# 5-3_fpga_bank_14-16.net
KiCad netlist of a schematic drawn in Altium Designer
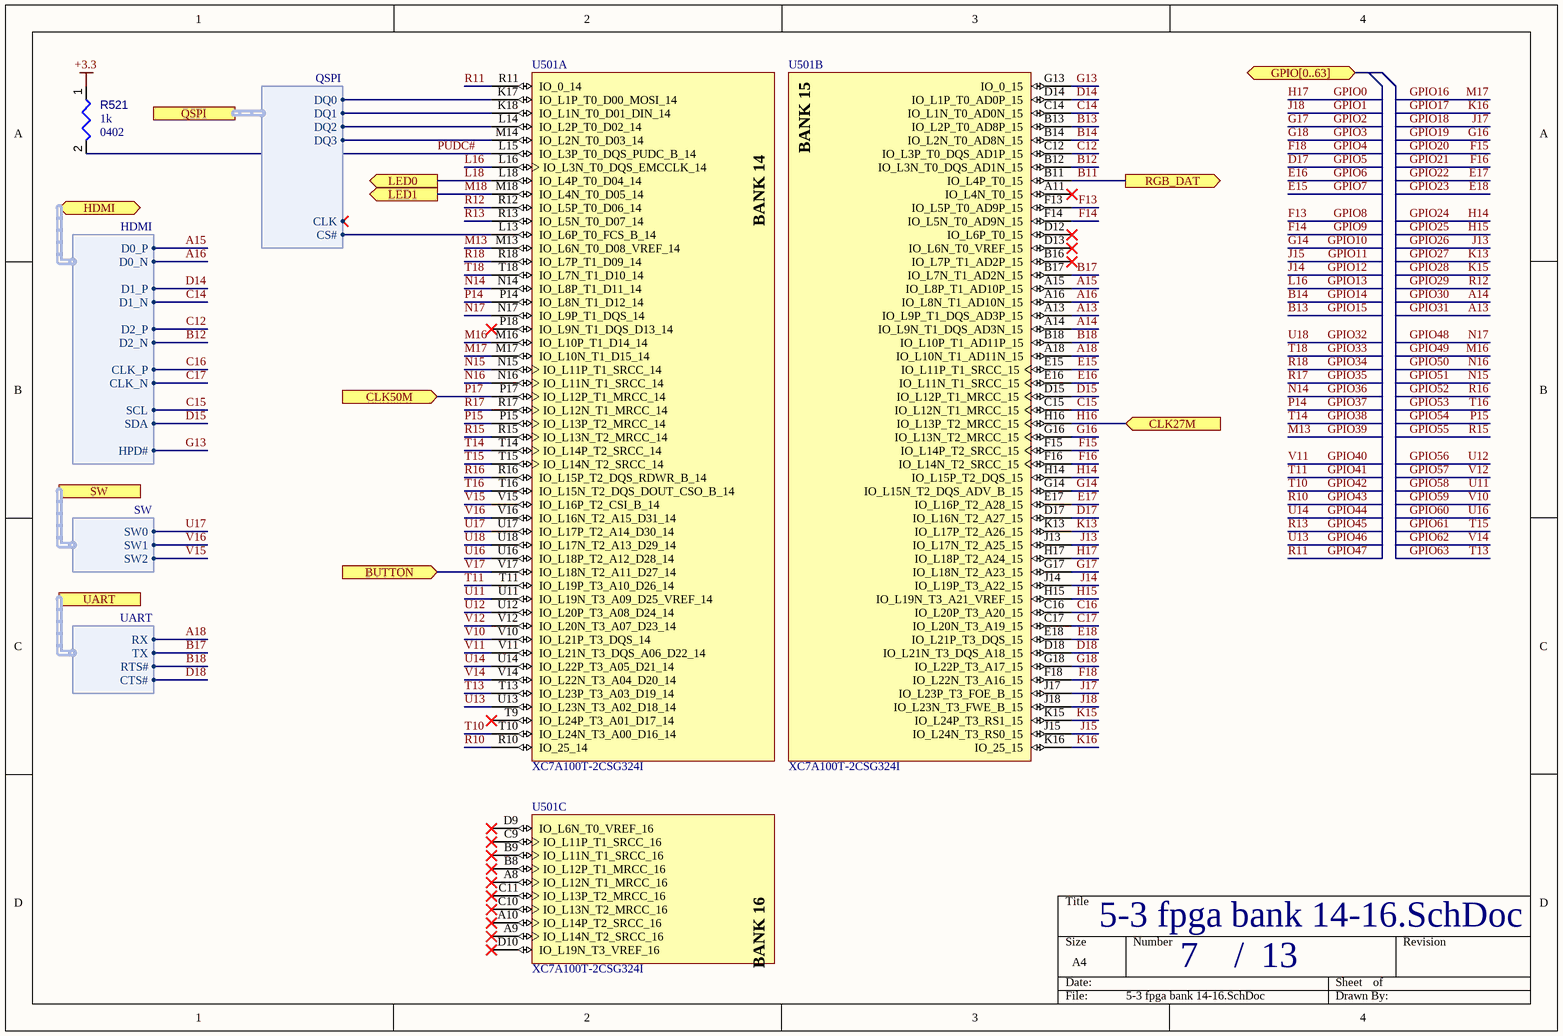
[diagram p0: 5-3 fpga bank 14-16.SchDoc]

(export (version "E")
  (design (tool "Eeschema 10.0.6"))
  (components
    (comp (ref "R521")
      (value "1k")
      (footprint "RESC0402(1005)_L")
      (description "Resistor")
      (fields (field (name "CASE/PACKAGE") "0402") (field (name "Comment") "Resistors,0402,1k"))
      (libsource (lib "UBC Uncrewed Aircraft Systems") (part "RES-2"))
    )
    (comp (ref "U501")
      (value "XC7A100T-2CSG324I")
      (footprint "CSG324")
      (description "Artix-7 FPGA, 210 User I/Os, 0 GTP, 324-Ball BGA, Speed Grade 2, Extended Grade, Pb-Free")
      (fields (field (name "MANUFACTURER") "Xilinx") (field (name "GENERIC PART NUMBER") "XC7A100T"))
      (libsource (lib "") (part "XNLX-XC7A100T-XNLX-CSG324_1"))
    )
  )
  (nets
    (net (code "5") (name "+3.3") (class "Default")
      (node (ref "R521") (pin "1") (pinfunction "1_1") (pintype "passive"))
    )
    (net (code "6") (name "/A15") (class "Default")
      (node (ref "U501") (pin "A15") (pinfunction "IO_L8P_T1_AD10P_15_A15") (pintype "bidirectional"))
    )
    (net (code "7") (name "/A16") (class "Default")
      (node (ref "U501") (pin "A16") (pinfunction "IO_L8N_T1_AD10N_15_A16") (pintype "bidirectional"))
    )
    (net (code "8") (name "/A18") (class "Default")
      (node (ref "U501") (pin "A18") (pinfunction "IO_L10N_T1_AD11N_15_A18") (pintype "bidirectional"))
    )
    (net (code "9") (name "/B11") (class "Default")
      (node (ref "U501") (pin "B11") (pinfunction "IO_L4P_T0_15_B11") (pintype "bidirectional"))
    )
    (net (code "10") (name "/B12") (class "Default")
      (node (ref "U501") (pin "B12") (pinfunction "IO_L3N_T0_DQS_AD1N_15_B12") (pintype "bidirectional"))
    )
    (net (code "11") (name "/B17") (class "Default")
      (node (ref "U501") (pin "B17") (pinfunction "IO_L7N_T1_AD2N_15_B17") (pintype "bidirectional"))
    )
    (net (code "12") (name "/B18") (class "Default")
      (node (ref "U501") (pin "B18") (pinfunction "IO_L10P_T1_AD11P_15_B18") (pintype "bidirectional"))
    )
    (net (code "13") (name "/C12") (class "Default")
      (node (ref "U501") (pin "C12") (pinfunction "IO_L3P_T0_DQS_AD1P_15_C12") (pintype "bidirectional"))
    )
    (net (code "14") (name "/C14") (class "Default")
      (node (ref "U501") (pin "C14") (pinfunction "IO_L1N_T0_AD0N_15_C14") (pintype "bidirectional"))
    )
    (net (code "15") (name "/C15") (class "Default")
      (node (ref "U501") (pin "C15") (pinfunction "IO_L12N_T1_MRCC_15_C15") (pintype "bidirectional"))
    )
    (net (code "16") (name "/C16") (class "Default")
      (node (ref "U501") (pin "C16") (pinfunction "IO_L20P_T3_A20_15_C16") (pintype "bidirectional"))
    )
    (net (code "17") (name "/C17") (class "Default")
      (node (ref "U501") (pin "C17") (pinfunction "IO_L20N_T3_A19_15_C17") (pintype "bidirectional"))
    )
    (net (code "18") (name "/CS#") (class "Default")
      (node (ref "U501") (pin "L13") (pinfunction "IO_L6P_T0_FCS_B_14_L13") (pintype "bidirectional"))
    )
    (net (code "19") (name "/D14") (class "Default")
      (node (ref "U501") (pin "D14") (pinfunction "IO_L1P_T0_AD0P_15_D14") (pintype "bidirectional"))
    )
    (net (code "20") (name "/D15") (class "Default")
      (node (ref "U501") (pin "D15") (pinfunction "IO_L12P_T1_MRCC_15_D15") (pintype "bidirectional"))
    )
    (net (code "21") (name "/D18") (class "Default")
      (node (ref "U501") (pin "D18") (pinfunction "IO_L21N_T3_DQS_A18_15_D18") (pintype "bidirectional"))
    )
    (net (code "22") (name "/DQ0") (class "Default")
      (node (ref "U501") (pin "K17") (pinfunction "IO_L1P_T0_D00_MOSI_14_K17") (pintype "bidirectional"))
    )
    (net (code "23") (name "/DQ1") (class "Default")
      (node (ref "U501") (pin "K18") (pinfunction "IO_L1N_T0_D01_DIN_14_K18") (pintype "bidirectional"))
    )
    (net (code "24") (name "/DQ2") (class "Default")
      (node (ref "U501") (pin "L14") (pinfunction "IO_L2P_T0_D02_14_L14") (pintype "bidirectional"))
    )
    (net (code "25") (name "/DQ3") (class "Default")
      (node (ref "U501") (pin "M14") (pinfunction "IO_L2N_T0_D03_14_M14") (pintype "bidirectional"))
    )
    (net (code "26") (name "/G13") (class "Default")
      (node (ref "U501") (pin "G13") (pinfunction "IO_0_15_G13") (pintype "bidirectional"))
    )
    (net (code "27") (name "/GPIO0") (class "Default")
      (node (ref "U501") (pin "H17") (pinfunction "IO_L18P_T2_A24_15_H17") (pintype "bidirectional"))
    )
    (net (code "28") (name "/GPIO1") (class "Default")
      (node (ref "U501") (pin "J18") (pinfunction "IO_L23N_T3_FWE_B_15_J18") (pintype "bidirectional"))
    )
    (net (code "29") (name "/GPIO2") (class "Default")
      (node (ref "U501") (pin "G17") (pinfunction "IO_L18N_T2_A23_15_G17") (pintype "bidirectional"))
    )
    (net (code "30") (name "/GPIO3") (class "Default")
      (node (ref "U501") (pin "G18") (pinfunction "IO_L22P_T3_A17_15_G18") (pintype "bidirectional"))
    )
    (net (code "31") (name "/GPIO4") (class "Default")
      (node (ref "U501") (pin "F18") (pinfunction "IO_L22N_T3_A16_15_F18") (pintype "bidirectional"))
    )
    (net (code "32") (name "/GPIO5") (class "Default")
      (node (ref "U501") (pin "D17") (pinfunction "IO_L16N_T2_A27_15_D17") (pintype "bidirectional"))
    )
    (net (code "33") (name "/GPIO6") (class "Default")
      (node (ref "U501") (pin "E16") (pinfunction "IO_L11N_T1_SRCC_15_E16") (pintype "bidirectional"))
    )
    (net (code "34") (name "/GPIO7") (class "Default")
      (node (ref "U501") (pin "E15") (pinfunction "IO_L11P_T1_SRCC_15_E15") (pintype "bidirectional"))
    )
    (net (code "35") (name "/GPIO8") (class "Default")
      (node (ref "U501") (pin "F13") (pinfunction "IO_L5P_T0_AD9P_15_F13") (pintype "bidirectional"))
    )
    (net (code "36") (name "/GPIO9") (class "Default")
      (node (ref "U501") (pin "F14") (pinfunction "IO_L5N_T0_AD9N_15_F14") (pintype "bidirectional"))
    )
    (net (code "37") (name "/GPIO10") (class "Default")
      (node (ref "U501") (pin "G14") (pinfunction "IO_L15N_T2_DQS_ADV_B_15_G14") (pintype "bidirectional"))
    )
    (net (code "38") (name "/GPIO11") (class "Default")
      (node (ref "U501") (pin "J15") (pinfunction "IO_L24N_T3_RS0_15_J15") (pintype "bidirectional"))
    )
    (net (code "39") (name "/GPIO12") (class "Default")
      (node (ref "U501") (pin "J14") (pinfunction "IO_L19P_T3_A22_15_J14") (pintype "bidirectional"))
    )
    (net (code "40") (name "/GPIO13") (class "Default")
      (node (ref "U501") (pin "L16") (pinfunction "IO_L3N_T0_DQS_EMCCLK_14_L16") (pintype "bidirectional"))
    )
    (net (code "41") (name "/GPIO14") (class "Default")
      (node (ref "U501") (pin "B14") (pinfunction "IO_L2N_T0_AD8N_15_B14") (pintype "bidirectional"))
    )
    (net (code "42") (name "/GPIO15") (class "Default")
      (node (ref "U501") (pin "B13") (pinfunction "IO_L2P_T0_AD8P_15_B13") (pintype "bidirectional"))
    )
    (net (code "43") (name "/GPIO16") (class "Default")
      (node (ref "U501") (pin "M17") (pinfunction "IO_L10N_T1_D15_14_M17") (pintype "bidirectional"))
    )
    (net (code "44") (name "/GPIO17") (class "Default")
      (node (ref "U501") (pin "K16") (pinfunction "IO_25_15_K16") (pintype "bidirectional"))
    )
    (net (code "45") (name "/GPIO18") (class "Default")
      (node (ref "U501") (pin "J17") (pinfunction "IO_L23P_T3_FOE_B_15_J17") (pintype "bidirectional"))
    )
    (net (code "46") (name "/GPIO19") (class "Default")
      (node (ref "U501") (pin "G16") (pinfunction "IO_L13N_T2_MRCC_15_G16") (pintype "bidirectional"))
    )
    (net (code "47") (name "/GPIO20") (class "Default")
      (node (ref "U501") (pin "F15") (pinfunction "IO_L14P_T2_SRCC_15_F15") (pintype "bidirectional"))
    )
    (net (code "48") (name "/GPIO21") (class "Default")
      (node (ref "U501") (pin "F16") (pinfunction "IO_L14N_T2_SRCC_15_F16") (pintype "bidirectional"))
    )
    (net (code "49") (name "/GPIO22") (class "Default")
      (node (ref "U501") (pin "E17") (pinfunction "IO_L16P_T2_A28_15_E17") (pintype "bidirectional"))
    )
    (net (code "50") (name "/GPIO23") (class "Default")
      (node (ref "U501") (pin "E18") (pinfunction "IO_L21P_T3_DQS_15_E18") (pintype "bidirectional"))
    )
    (net (code "51") (name "/GPIO24") (class "Default")
      (node (ref "U501") (pin "H14") (pinfunction "IO_L15P_T2_DQS_15_H14") (pintype "bidirectional"))
    )
    (net (code "52") (name "/GPIO25") (class "Default")
      (node (ref "U501") (pin "H15") (pinfunction "IO_L19N_T3_A21_VREF_15_H15") (pintype "bidirectional"))
    )
    (net (code "53") (name "/GPIO26") (class "Default")
      (node (ref "U501") (pin "J13") (pinfunction "IO_L17N_T2_A25_15_J13") (pintype "bidirectional"))
    )
    (net (code "54") (name "/GPIO27") (class "Default")
      (node (ref "U501") (pin "K13") (pinfunction "IO_L17P_T2_A26_15_K13") (pintype "bidirectional"))
    )
    (net (code "55") (name "/GPIO28") (class "Default")
      (node (ref "U501") (pin "K15") (pinfunction "IO_L24P_T3_RS1_15_K15") (pintype "bidirectional"))
    )
    (net (code "56") (name "/GPIO29") (class "Default")
      (node (ref "U501") (pin "R12") (pinfunction "IO_L5P_T0_D06_14_R12") (pintype "bidirectional"))
    )
    (net (code "57") (name "/GPIO30") (class "Default")
      (node (ref "U501") (pin "A14") (pinfunction "IO_L9N_T1_DQS_AD3N_15_A14") (pintype "bidirectional"))
    )
    (net (code "58") (name "/GPIO31") (class "Default")
      (node (ref "U501") (pin "A13") (pinfunction "IO_L9P_T1_DQS_AD3P_15_A13") (pintype "bidirectional"))
    )
    (net (code "59") (name "/GPIO32") (class "Default")
      (node (ref "U501") (pin "U18") (pinfunction "IO_L17N_T2_A13_D29_14_U18") (pintype "bidirectional"))
    )
    (net (code "60") (name "/GPIO33") (class "Default")
      (node (ref "U501") (pin "T18") (pinfunction "IO_L7N_T1_D10_14_T18") (pintype "bidirectional"))
    )
    (net (code "61") (name "/GPIO34") (class "Default")
      (node (ref "U501") (pin "R18") (pinfunction "IO_L7P_T1_D09_14_R18") (pintype "bidirectional"))
    )
    (net (code "62") (name "/GPIO35") (class "Default")
      (node (ref "U501") (pin "R17") (pinfunction "IO_L12N_T1_MRCC_14_R17") (pintype "bidirectional"))
    )
    (net (code "63") (name "/GPIO36") (class "Default")
      (node (ref "U501") (pin "N14") (pinfunction "IO_L8P_T1_D11_14_N14") (pintype "bidirectional"))
    )
    (net (code "64") (name "/GPIO37") (class "Default")
      (node (ref "U501") (pin "P14") (pinfunction "IO_L8N_T1_D12_14_P14") (pintype "bidirectional"))
    )
    (net (code "65") (name "/GPIO38") (class "Default")
      (node (ref "U501") (pin "T14") (pinfunction "IO_L14P_T2_SRCC_14_T14") (pintype "bidirectional"))
    )
    (net (code "66") (name "/GPIO39") (class "Default")
      (node (ref "U501") (pin "M13") (pinfunction "IO_L6N_T0_D08_VREF_14_M13") (pintype "bidirectional"))
    )
    (net (code "67") (name "/GPIO40") (class "Default")
      (node (ref "U501") (pin "V11") (pinfunction "IO_L21N_T3_DQS_A06_D22_14_V11") (pintype "bidirectional"))
    )
    (net (code "68") (name "/GPIO41") (class "Default")
      (node (ref "U501") (pin "T11") (pinfunction "IO_L19P_T3_A10_D26_14_T11") (pintype "bidirectional"))
    )
    (net (code "69") (name "/GPIO42") (class "Default")
      (node (ref "U501") (pin "T10") (pinfunction "IO_L24N_T3_A00_D16_14_T10") (pintype "bidirectional"))
    )
    (net (code "70") (name "/GPIO43") (class "Default")
      (node (ref "U501") (pin "R10") (pinfunction "IO_25_14_R10") (pintype "bidirectional"))
    )
    (net (code "71") (name "/GPIO44") (class "Default")
      (node (ref "U501") (pin "U14") (pinfunction "IO_L22P_T3_A05_D21_14_U14") (pintype "bidirectional"))
    )
    (net (code "72") (name "/GPIO45") (class "Default")
      (node (ref "U501") (pin "R13") (pinfunction "IO_L5N_T0_D07_14_R13") (pintype "bidirectional"))
    )
    (net (code "73") (name "/GPIO46") (class "Default")
      (node (ref "U501") (pin "U13") (pinfunction "IO_L23N_T3_A02_D18_14_U13") (pintype "bidirectional"))
    )
    (net (code "74") (name "/GPIO47") (class "Default")
      (node (ref "U501") (pin "R11") (pinfunction "IO_0_14_R11") (pintype "bidirectional"))
    )
    (net (code "75") (name "/GPIO48") (class "Default")
      (node (ref "U501") (pin "N17") (pinfunction "IO_L9P_T1_DQS_14_N17") (pintype "bidirectional"))
    )
    (net (code "76") (name "/GPIO49") (class "Default")
      (node (ref "U501") (pin "M16") (pinfunction "IO_L10P_T1_D14_14_M16") (pintype "bidirectional"))
    )
    (net (code "77") (name "/GPIO50") (class "Default")
      (node (ref "U501") (pin "N16") (pinfunction "IO_L11N_T1_SRCC_14_N16") (pintype "bidirectional"))
    )
    (net (code "78") (name "/GPIO51") (class "Default")
      (node (ref "U501") (pin "N15") (pinfunction "IO_L11P_T1_SRCC_14_N15") (pintype "bidirectional"))
    )
    (net (code "79") (name "/GPIO52") (class "Default")
      (node (ref "U501") (pin "R16") (pinfunction "IO_L15P_T2_DQS_RDWR_B_14_R16") (pintype "bidirectional"))
    )
    (net (code "80") (name "/GPIO53") (class "Default")
      (node (ref "U501") (pin "T16") (pinfunction "IO_L15N_T2_DQS_DOUT_CSO_B_14_T16") (pintype "bidirectional"))
    )
    (net (code "81") (name "/GPIO54") (class "Default")
      (node (ref "U501") (pin "P15") (pinfunction "IO_L13P_T2_MRCC_14_P15") (pintype "bidirectional"))
    )
    (net (code "82") (name "/GPIO55") (class "Default")
      (node (ref "U501") (pin "R15") (pinfunction "IO_L13N_T2_MRCC_14_R15") (pintype "bidirectional"))
    )
    (net (code "83") (name "/GPIO56") (class "Default")
      (node (ref "U501") (pin "U12") (pinfunction "IO_L20P_T3_A08_D24_14_U12") (pintype "bidirectional"))
    )
    (net (code "84") (name "/GPIO57") (class "Default")
      (node (ref "U501") (pin "V12") (pinfunction "IO_L20N_T3_A07_D23_14_V12") (pintype "bidirectional"))
    )
    (net (code "85") (name "/GPIO58") (class "Default")
      (node (ref "U501") (pin "U11") (pinfunction "IO_L19N_T3_A09_D25_VREF_14_U11") (pintype "bidirectional"))
    )
    (net (code "86") (name "/GPIO59") (class "Default")
      (node (ref "U501") (pin "V10") (pinfunction "IO_L21P_T3_DQS_14_V10") (pintype "bidirectional"))
    )
    (net (code "87") (name "/GPIO60") (class "Default")
      (node (ref "U501") (pin "U16") (pinfunction "IO_L18P_T2_A12_D28_14_U16") (pintype "bidirectional"))
    )
    (net (code "88") (name "/GPIO61") (class "Default")
      (node (ref "U501") (pin "T15") (pinfunction "IO_L14N_T2_SRCC_14_T15") (pintype "bidirectional"))
    )
    (net (code "89") (name "/GPIO62") (class "Default")
      (node (ref "U501") (pin "V14") (pinfunction "IO_L22N_T3_A04_D20_14_V14") (pintype "bidirectional"))
    )
    (net (code "90") (name "/GPIO63") (class "Default")
      (node (ref "U501") (pin "T13") (pinfunction "IO_L23P_T3_A03_D19_14_T13") (pintype "bidirectional"))
    )
    (net (code "92") (name "/H16") (class "Default")
      (node (ref "U501") (pin "H16") (pinfunction "IO_L13P_T2_MRCC_15_H16") (pintype "bidirectional"))
    )
    (net (code "93") (name "/L18") (class "Default")
      (node (ref "U501") (pin "L18") (pinfunction "IO_L4P_T0_D04_14_L18") (pintype "bidirectional"))
    )
    (net (code "94") (name "/M18") (class "Default")
      (node (ref "U501") (pin "M18") (pinfunction "IO_L4N_T0_D05_14_M18") (pintype "bidirectional"))
    )
    (net (code "95") (name "/P17") (class "Default")
      (node (ref "U501") (pin "P17") (pinfunction "IO_L12P_T1_MRCC_14_P17") (pintype "bidirectional"))
    )
    (net (code "96") (name "/PUDC#") (class "Default")
      (node (ref "R521") (pin "2") (pinfunction "2_2") (pintype "passive"))
      (node (ref "U501") (pin "L15") (pinfunction "IO_L3P_T0_DQS_PUDC_B_14_L15") (pintype "bidirectional"))
    )
    (net (code "97") (name "/U17") (class "Default")
      (node (ref "U501") (pin "U17") (pinfunction "IO_L17P_T2_A14_D30_14_U17") (pintype "bidirectional"))
    )
    (net (code "98") (name "/V15") (class "Default")
      (node (ref "U501") (pin "V15") (pinfunction "IO_L16P_T2_CSI_B_14_V15") (pintype "bidirectional"))
    )
    (net (code "99") (name "/V16") (class "Default")
      (node (ref "U501") (pin "V16") (pinfunction "IO_L16N_T2_A15_D31_14_V16") (pintype "bidirectional"))
    )
    (net (code "100") (name "/V17") (class "Default")
      (node (ref "U501") (pin "V17") (pinfunction "IO_L18N_T2_A11_D27_14_V17") (pintype "bidirectional"))
    )
    (net (code "105") (name "unconnected-(U501A-IO_L9N_T1_DQS_D13_14-PadP18)") (class "Default")
      (node (ref "U501") (pin "P18") (pinfunction "IO_L9N_T1_DQS_D13_14_P18") (pintype "bidirectional+no_connect"))
    )
    (net (code "106") (name "unconnected-(U501A-IO_L24P_T3_A01_D17_14-PadT9)") (class "Default")
      (node (ref "U501") (pin "T9") (pinfunction "IO_L24P_T3_A01_D17_14_T9") (pintype "bidirectional+no_connect"))
    )
    (net (code "107") (name "unconnected-(U501B-IO_L4N_T0_15-PadA11)") (class "Default")
      (node (ref "U501") (pin "A11") (pinfunction "IO_L4N_T0_15_A11") (pintype "bidirectional+no_connect"))
    )
    (net (code "108") (name "unconnected-(U501B-IO_L6N_T0_VREF_15-PadD13)") (class "Default")
      (node (ref "U501") (pin "D13") (pinfunction "IO_L6N_T0_VREF_15_D13") (pintype "bidirectional+no_connect"))
    )
    (net (code "109") (name "unconnected-(U501B-IO_L6P_T0_15-PadD12)") (class "Default")
      (node (ref "U501") (pin "D12") (pinfunction "IO_L6P_T0_15_D12") (pintype "bidirectional+no_connect"))
    )
    (net (code "110") (name "unconnected-(U501B-IO_L7P_T1_AD2P_15-PadB16)") (class "Default")
      (node (ref "U501") (pin "B16") (pinfunction "IO_L7P_T1_AD2P_15_B16") (pintype "bidirectional+no_connect"))
    )
    (net (code "111") (name "unconnected-(U501C-IO_L6N_T0_VREF_16-PadD9)") (class "Default")
      (node (ref "U501") (pin "D9") (pinfunction "IO_L6N_T0_VREF_16_D9") (pintype "bidirectional+no_connect"))
    )
    (net (code "112") (name "unconnected-(U501C-IO_L11N_T1_SRCC_16-PadB9)") (class "Default")
      (node (ref "U501") (pin "B9") (pinfunction "IO_L11N_T1_SRCC_16_B9") (pintype "bidirectional+no_connect"))
    )
    (net (code "113") (name "unconnected-(U501C-IO_L11P_T1_SRCC_16-PadC9)") (class "Default")
      (node (ref "U501") (pin "C9") (pinfunction "IO_L11P_T1_SRCC_16_C9") (pintype "bidirectional+no_connect"))
    )
    (net (code "114") (name "unconnected-(U501C-IO_L12N_T1_MRCC_16-PadA8)") (class "Default")
      (node (ref "U501") (pin "A8") (pinfunction "IO_L12N_T1_MRCC_16_A8") (pintype "bidirectional+no_connect"))
    )
    (net (code "115") (name "unconnected-(U501C-IO_L12P_T1_MRCC_16-PadB8)") (class "Default")
      (node (ref "U501") (pin "B8") (pinfunction "IO_L12P_T1_MRCC_16_B8") (pintype "bidirectional+no_connect"))
    )
    (net (code "116") (name "unconnected-(U501C-IO_L13N_T2_MRCC_16-PadC10)") (class "Default")
      (node (ref "U501") (pin "C10") (pinfunction "IO_L13N_T2_MRCC_16_C10") (pintype "bidirectional+no_connect"))
    )
    (net (code "117") (name "unconnected-(U501C-IO_L13P_T2_MRCC_16-PadC11)") (class "Default")
      (node (ref "U501") (pin "C11") (pinfunction "IO_L13P_T2_MRCC_16_C11") (pintype "bidirectional+no_connect"))
    )
    (net (code "118") (name "unconnected-(U501C-IO_L14N_T2_SRCC_16-PadA9)") (class "Default")
      (node (ref "U501") (pin "A9") (pinfunction "IO_L14N_T2_SRCC_16_A9") (pintype "bidirectional+no_connect"))
    )
    (net (code "119") (name "unconnected-(U501C-IO_L14P_T2_SRCC_16-PadA10)") (class "Default")
      (node (ref "U501") (pin "A10") (pinfunction "IO_L14P_T2_SRCC_16_A10") (pintype "bidirectional+no_connect"))
    )
    (net (code "120") (name "unconnected-(U501C-IO_L19N_T3_VREF_16-PadD10)") (class "Default")
      (node (ref "U501") (pin "D10") (pinfunction "IO_L19N_T3_VREF_16_D10") (pintype "bidirectional+no_connect"))
    )
  )
)
